# CAN_IF_Test.net
KiCad netlist of a schematic drawn in Altium Designer
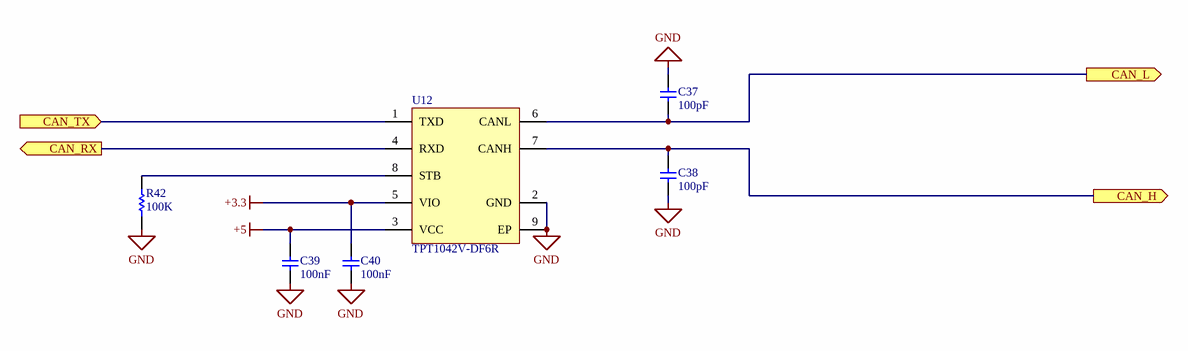
[diagram p0: CAN_IF_Test.SchDoc]

(export (version "E")
  (design (tool "Eeschema 10.0.6"))
  (components
    (comp (ref "C37")
      (value "100pF")
      (footprint "0603M")
      (description "Ceramic Capacitor 50V")
      (fields (field (name "Comment") "Cap Ceramic"))
      (libsource (lib "Plume") (part "Cap Ceramic"))
    )
    (comp (ref "C38")
      (value "100pF")
      (footprint "0603M")
      (description "Ceramic Capacitor 50V")
      (fields (field (name "Comment") "Cap Ceramic"))
      (libsource (lib "Plume") (part "Cap Ceramic"))
    )
    (comp (ref "C39")
      (value "100nF")
      (footprint "0603M-C")
      (description "Ceramic Capacitor 25V")
      (fields (field (name "Comment") "Cap Ceramic"))
      (libsource (lib "Plume") (part "Cap Ceramic"))
    )
    (comp (ref "C40")
      (value "100nF")
      (footprint "0603M-C")
      (description "Ceramic Capacitor 25V")
      (fields (field (name "Comment") "Cap Ceramic"))
      (libsource (lib "Plume") (part "Cap Ceramic"))
    )
    (comp (ref "R42")
      (value "100K")
      (footprint "0603M")
      (description "Resistor")
      (libsource (lib "Plume") (part "Resistor"))
    )
    (comp (ref "U12")
      (value "TPT1042V-DF6R")
      (footprint "HVSON8-0.65mm")
      (description "High-speed CAN transceiver with Standby mode and VIO")
      (libsource (lib "Plume") (part "TPT1042V"))
    )
  )
  (nets
    (net (code "1") (name "+3.3") (class "Default")
      (node (ref "C40") (pin "2") (pinfunction "2_2") (pintype "passive"))
      (node (ref "U12") (pin "5") (pinfunction "VIO_5") (pintype "passive"))
    )
    (net (code "2") (name "+5") (class "Default")
      (node (ref "C39") (pin "2") (pinfunction "2_2") (pintype "passive"))
      (node (ref "U12") (pin "3") (pinfunction "VCC_3") (pintype "passive"))
    )
    (net (code "3") (name "/CAN_H") (class "Default")
      (node (ref "C38") (pin "2") (pinfunction "2_2") (pintype "passive"))
      (node (ref "U12") (pin "7") (pinfunction "CANH_7") (pintype "passive"))
    )
    (net (code "4") (name "/CAN_L") (class "Default")
      (node (ref "C37") (pin "2") (pinfunction "2_2") (pintype "passive"))
      (node (ref "U12") (pin "6") (pinfunction "CANL_6") (pintype "passive"))
    )
    (net (code "5") (name "/CAN_RX") (class "Default")
      (node (ref "U12") (pin "4") (pinfunction "RXD_4") (pintype "passive"))
    )
    (net (code "6") (name "/CAN_TX") (class "Default")
      (node (ref "U12") (pin "1") (pinfunction "TXD_1") (pintype "passive"))
    )
    (net (code "7") (name "GND") (class "Default")
      (node (ref "C37") (pin "1") (pinfunction "1_1") (pintype "passive"))
      (node (ref "C38") (pin "1") (pinfunction "1_1") (pintype "passive"))
      (node (ref "C39") (pin "1") (pinfunction "1_1") (pintype "passive"))
      (node (ref "C40") (pin "1") (pinfunction "1_1") (pintype "passive"))
      (node (ref "R42") (pin "1") (pinfunction "1_1") (pintype "passive"))
      (node (ref "U12") (pin "2") (pinfunction "GND_2") (pintype "passive"))
      (node (ref "U12") (pin "9") (pinfunction "EP_9") (pintype "passive"))
    )
    (net (code "8") (name "Net-(U12-STB)") (class "Default")
      (node (ref "R42") (pin "2") (pinfunction "2_2") (pintype "passive"))
      (node (ref "U12") (pin "8") (pinfunction "STB_8") (pintype "passive"))
    )
  )
)
